# GL42.net
KiCad netlist of a schematic drawn in EAGLE
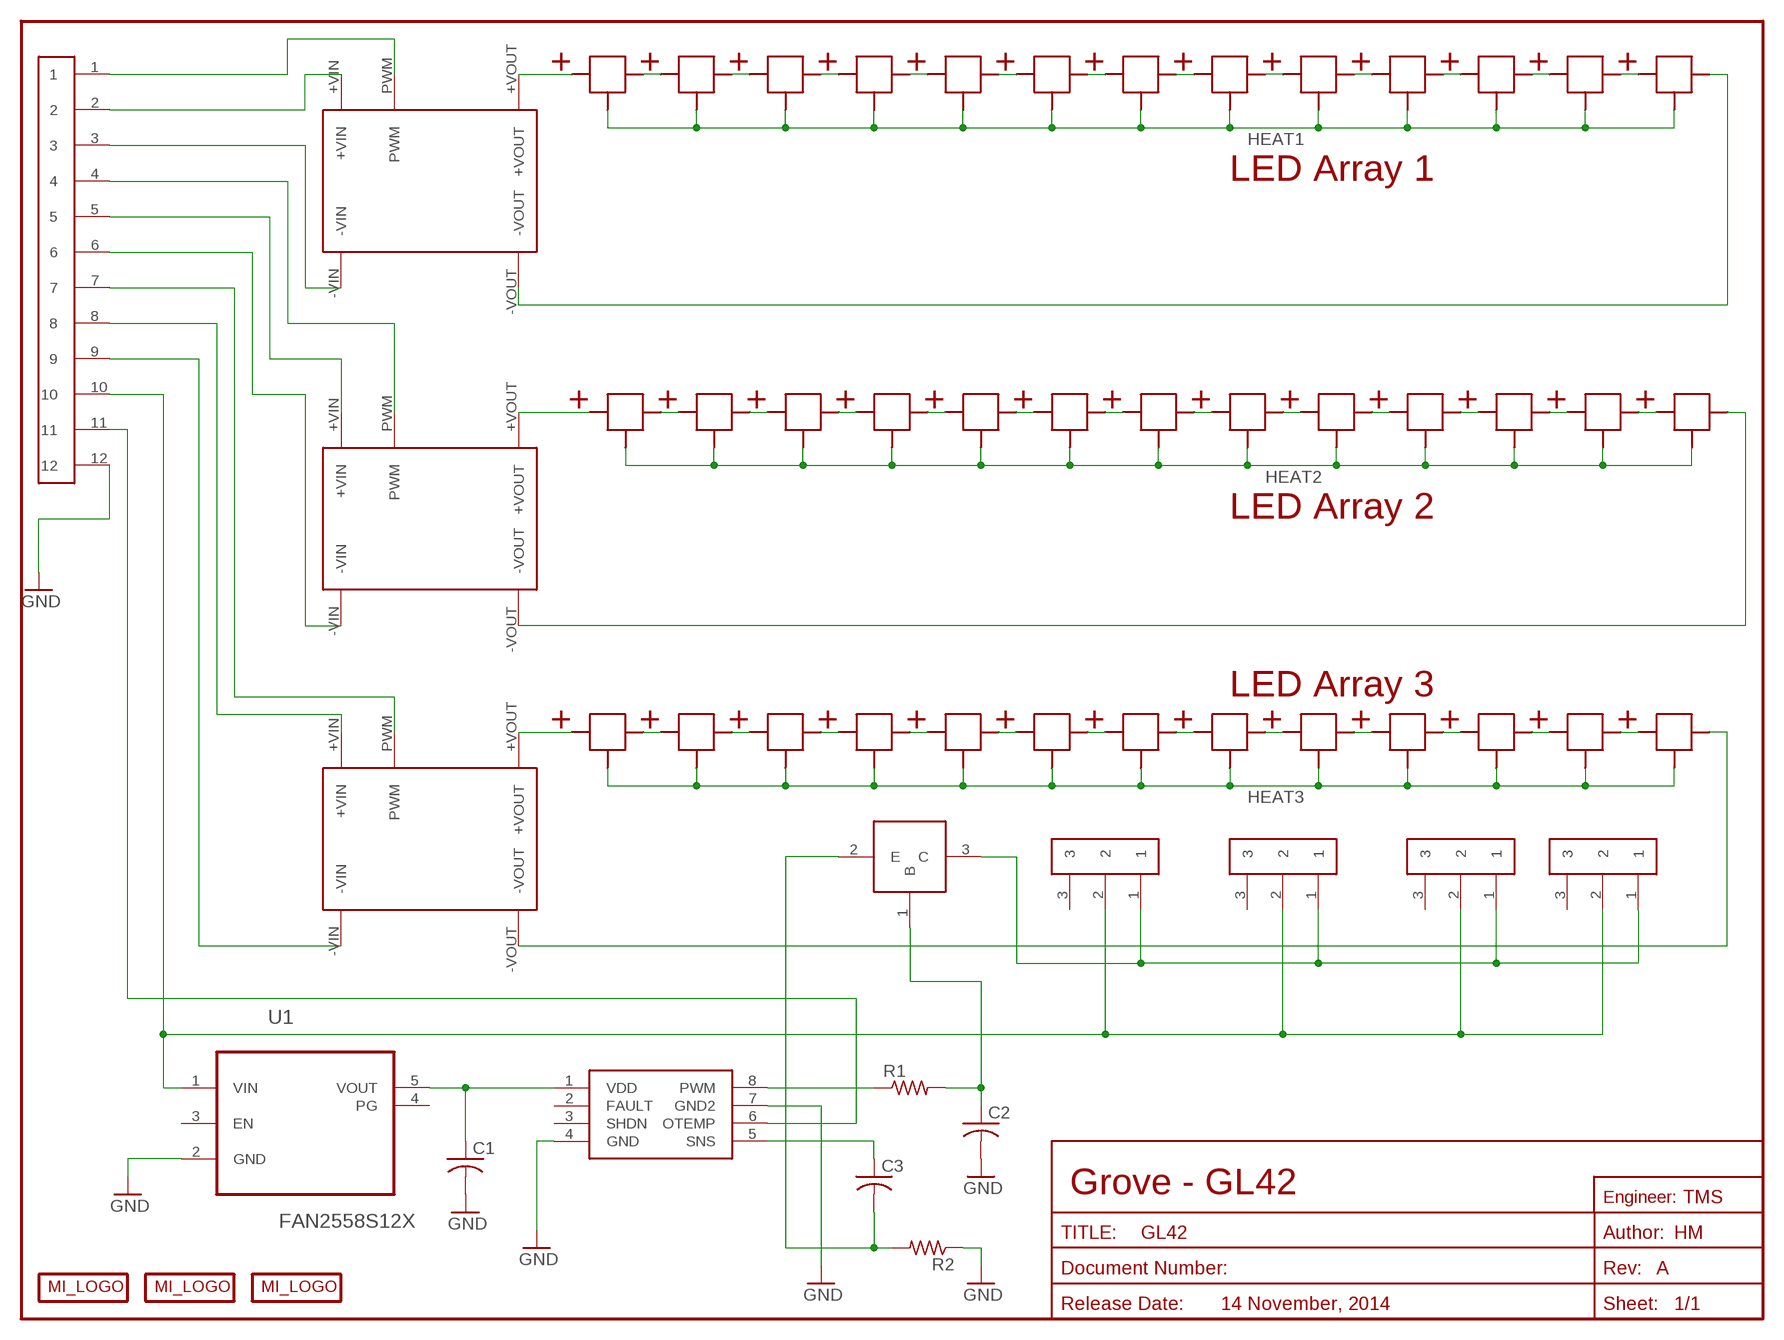
[diagram p0: schematic, sheet 1]

(export (version "E")
  (design (tool "Eeschema 10.0.6"))
  (components
    (comp (ref "C1")
      (value "C-USC1206")
      (footprint "eagle-import:C1206")
      (libsource (lib "eagle-import") (part "C-USC1206"))
    )
    (comp (ref "C2")
      (value "C-USC1206")
      (footprint "eagle-import:C1206")
      (libsource (lib "eagle-import") (part "C-USC1206"))
    )
    (comp (ref "C3")
      (value "C-USC1206")
      (footprint "eagle-import:C1206")
      (libsource (lib "eagle-import") (part "C-USC1206"))
    )
    (comp (ref "R1")
      (value "R-US_R1206")
      (footprint "eagle-import:R1206")
      (libsource (lib "eagle-import") (part "R-US_R1206"))
    )
    (comp (ref "R2")
      (value "R-US_R2512")
      (footprint "eagle-import:R2512")
      (libsource (lib "eagle-import") (part "R-US_R2512"))
    )
    (comp (ref "U$1")
      (value "CREE_XP")
      (footprint "eagle-import:XP")
      (libsource (lib "eagle-import") (part "CREE_XP"))
    )
    (comp (ref "U$2")
      (value "CREE_XP")
      (footprint "eagle-import:XP")
      (libsource (lib "eagle-import") (part "CREE_XP"))
    )
    (comp (ref "U$3")
      (value "CREE_XP")
      (footprint "eagle-import:XP")
      (libsource (lib "eagle-import") (part "CREE_XP"))
    )
    (comp (ref "U$4")
      (value "CREE_XP")
      (footprint "eagle-import:XP")
      (libsource (lib "eagle-import") (part "CREE_XP"))
    )
    (comp (ref "U$5")
      (value "CREE_XP")
      (footprint "eagle-import:XP")
      (libsource (lib "eagle-import") (part "CREE_XP"))
    )
    (comp (ref "U$6")
      (value "CREE_XP")
      (footprint "eagle-import:XP")
      (libsource (lib "eagle-import") (part "CREE_XP"))
    )
    (comp (ref "U$7")
      (value "CREE_XP")
      (footprint "eagle-import:XP")
      (libsource (lib "eagle-import") (part "CREE_XP"))
    )
    (comp (ref "U$8")
      (value "CREE_XP")
      (footprint "eagle-import:XP")
      (libsource (lib "eagle-import") (part "CREE_XP"))
    )
    (comp (ref "U$9")
      (value "CREE_XP")
      (footprint "eagle-import:XP")
      (libsource (lib "eagle-import") (part "CREE_XP"))
    )
    (comp (ref "U$10")
      (value "CREE_XP")
      (footprint "eagle-import:XP")
      (libsource (lib "eagle-import") (part "CREE_XP"))
    )
    (comp (ref "U$11")
      (value "CREE_XP")
      (footprint "eagle-import:XP")
      (libsource (lib "eagle-import") (part "CREE_XP"))
    )
    (comp (ref "U$12")
      (value "CREE_XP")
      (footprint "eagle-import:XP")
      (libsource (lib "eagle-import") (part "CREE_XP"))
    )
    (comp (ref "U$13")
      (value "CREE_XP")
      (footprint "eagle-import:XP")
      (libsource (lib "eagle-import") (part "CREE_XP"))
    )
    (comp (ref "U$14")
      (value "TC652")
      (footprint "eagle-import:MSOP8")
      (libsource (lib "eagle-import") (part "TC652"))
    )
    (comp (ref "U$15")
      (value "PH14SMT")
      (footprint "eagle-import:PH14SMT")
      (libsource (lib "eagle-import") (part "PH14SMT"))
    )
    (comp (ref "U$16")
      (value "LDD_HSMT")
      (footprint "eagle-import:LDD_HSMT")
      (libsource (lib "eagle-import") (part "LDD_HSMT"))
    )
    (comp (ref "U$17")
      (value "LDD_HSMT")
      (footprint "eagle-import:LDD_HSMT")
      (libsource (lib "eagle-import") (part "LDD_HSMT"))
    )
    (comp (ref "U$18")
      (value "LDD_HSMT")
      (footprint "eagle-import:LDD_HSMT")
      (libsource (lib "eagle-import") (part "LDD_HSMT"))
    )
    (comp (ref "U$19")
      (value "CREE_XP")
      (footprint "eagle-import:XP")
      (libsource (lib "eagle-import") (part "CREE_XP"))
    )
    (comp (ref "U$20")
      (value "CREE_XP")
      (footprint "eagle-import:XP")
      (libsource (lib "eagle-import") (part "CREE_XP"))
    )
    (comp (ref "U$21")
      (value "CREE_XP")
      (footprint "eagle-import:XP")
      (libsource (lib "eagle-import") (part "CREE_XP"))
    )
    (comp (ref "U$22")
      (value "CREE_XP")
      (footprint "eagle-import:XP")
      (libsource (lib "eagle-import") (part "CREE_XP"))
    )
    (comp (ref "U$23")
      (value "CREE_XP")
      (footprint "eagle-import:XP")
      (libsource (lib "eagle-import") (part "CREE_XP"))
    )
    (comp (ref "U$24")
      (value "CREE_XP")
      (footprint "eagle-import:XP")
      (libsource (lib "eagle-import") (part "CREE_XP"))
    )
    (comp (ref "U$25")
      (value "CREE_XP")
      (footprint "eagle-import:XP")
      (libsource (lib "eagle-import") (part "CREE_XP"))
    )
    (comp (ref "U$26")
      (value "CREE_XP")
      (footprint "eagle-import:XP")
      (libsource (lib "eagle-import") (part "CREE_XP"))
    )
    (comp (ref "U$27")
      (value "CREE_XP")
      (footprint "eagle-import:XP")
      (libsource (lib "eagle-import") (part "CREE_XP"))
    )
    (comp (ref "U$28")
      (value "CREE_XP")
      (footprint "eagle-import:XP")
      (libsource (lib "eagle-import") (part "CREE_XP"))
    )
    (comp (ref "U$29")
      (value "CREE_XP")
      (footprint "eagle-import:XP")
      (libsource (lib "eagle-import") (part "CREE_XP"))
    )
    (comp (ref "U$30")
      (value "CREE_XP")
      (footprint "eagle-import:XP")
      (libsource (lib "eagle-import") (part "CREE_XP"))
    )
    (comp (ref "U$31")
      (value "CREE_XP")
      (footprint "eagle-import:XP")
      (libsource (lib "eagle-import") (part "CREE_XP"))
    )
    (comp (ref "U$32")
      (value "CREE_XP")
      (footprint "eagle-import:XP")
      (libsource (lib "eagle-import") (part "CREE_XP"))
    )
    (comp (ref "U$33")
      (value "CREE_XP")
      (footprint "eagle-import:XP")
      (libsource (lib "eagle-import") (part "CREE_XP"))
    )
    (comp (ref "U$34")
      (value "CREE_XP")
      (footprint "eagle-import:XP")
      (libsource (lib "eagle-import") (part "CREE_XP"))
    )
    (comp (ref "U$35")
      (value "CREE_XP")
      (footprint "eagle-import:XP")
      (libsource (lib "eagle-import") (part "CREE_XP"))
    )
    (comp (ref "U$36")
      (value "CREE_XP")
      (footprint "eagle-import:XP")
      (libsource (lib "eagle-import") (part "CREE_XP"))
    )
    (comp (ref "U$37")
      (value "CREE_XP")
      (footprint "eagle-import:XP")
      (libsource (lib "eagle-import") (part "CREE_XP"))
    )
    (comp (ref "U$38")
      (value "CREE_XP")
      (footprint "eagle-import:XP")
      (libsource (lib "eagle-import") (part "CREE_XP"))
    )
    (comp (ref "U$39")
      (value "CREE_XP")
      (footprint "eagle-import:XP")
      (libsource (lib "eagle-import") (part "CREE_XP"))
    )
    (comp (ref "U$40")
      (value "CREE_XP")
      (footprint "eagle-import:XP")
      (libsource (lib "eagle-import") (part "CREE_XP"))
    )
    (comp (ref "U$41")
      (value "CREE_XP")
      (footprint "eagle-import:XP")
      (libsource (lib "eagle-import") (part "CREE_XP"))
    )
    (comp (ref "U$42")
      (value "CREE_XP")
      (footprint "eagle-import:XP")
      (libsource (lib "eagle-import") (part "CREE_XP"))
    )
    (comp (ref "U$43")
      (value "CREE_XP")
      (footprint "eagle-import:XP")
      (libsource (lib "eagle-import") (part "CREE_XP"))
    )
    (comp (ref "U$44")
      (value "CREE_XP")
      (footprint "eagle-import:XP")
      (libsource (lib "eagle-import") (part "CREE_XP"))
    )
    (comp (ref "U$45")
      (value "NPN_POWERTRAN")
      (footprint "eagle-import:TO252")
      (libsource (lib "eagle-import") (part "NPN_POWERTRAN"))
    )
    (comp (ref "U$46")
      (value "PH3SMT")
      (footprint "eagle-import:PH3SMT")
      (libsource (lib "eagle-import") (part "PH3SMT"))
    )
    (comp (ref "U$47")
      (value "PH3SMT")
      (footprint "eagle-import:PH3SMT")
      (libsource (lib "eagle-import") (part "PH3SMT"))
    )
    (comp (ref "U$48")
      (value "PH3SMT")
      (footprint "eagle-import:PH3SMT")
      (libsource (lib "eagle-import") (part "PH3SMT"))
    )
    (comp (ref "U$49")
      (value "PH3SMT")
      (footprint "eagle-import:PH3SMT")
      (libsource (lib "eagle-import") (part "PH3SMT"))
    )
    (comp (ref "U$50")
      (value "MI_LOGO-GROVE")
      (footprint "eagle-import:GROVES_LOGO")
      (libsource (lib "eagle-import") (part "MI_LOGO-GROVE"))
    )
    (comp (ref "U$51")
      (value "MI_LOGO-NAME_TWO")
      (footprint "eagle-import:MI_LOGO_NAME_2")
      (libsource (lib "eagle-import") (part "MI_LOGO-NAME_TWO"))
    )
    (comp (ref "U$54")
      (value "MI_LOGO-2014_USA")
      (footprint "eagle-import:MACRIS_USA_LOGO")
      (libsource (lib "eagle-import") (part "MI_LOGO-2014_USA"))
    )
    (comp (ref "U1")
      (value "FAN2558S12X")
      (footprint "eagle-import:SOT95P280X145-5N")
      (libsource (lib "eagle-import") (part "FAN2558S12X"))
    )
  )
  (nets
    (net (code "1") (name "/HEAT1") (class "Default")
      (node (ref "U$1") (pin "THERMAL") (pinfunction "THERMAL_THERMAL") (pintype "bidirectional"))
      (node (ref "U$10") (pin "THERMAL") (pinfunction "THERMAL_THERMAL") (pintype "bidirectional"))
      (node (ref "U$11") (pin "THERMAL") (pinfunction "THERMAL_THERMAL") (pintype "bidirectional"))
      (node (ref "U$12") (pin "THERMAL") (pinfunction "THERMAL_THERMAL") (pintype "bidirectional"))
      (node (ref "U$13") (pin "THERMAL") (pinfunction "THERMAL_THERMAL") (pintype "bidirectional"))
      (node (ref "U$2") (pin "THERMAL") (pinfunction "THERMAL_THERMAL") (pintype "bidirectional"))
      (node (ref "U$3") (pin "THERMAL") (pinfunction "THERMAL_THERMAL") (pintype "bidirectional"))
      (node (ref "U$4") (pin "THERMAL") (pinfunction "THERMAL_THERMAL") (pintype "bidirectional"))
      (node (ref "U$5") (pin "THERMAL") (pinfunction "THERMAL_THERMAL") (pintype "bidirectional"))
      (node (ref "U$6") (pin "THERMAL") (pinfunction "THERMAL_THERMAL") (pintype "bidirectional"))
      (node (ref "U$7") (pin "THERMAL") (pinfunction "THERMAL_THERMAL") (pintype "bidirectional"))
      (node (ref "U$8") (pin "THERMAL") (pinfunction "THERMAL_THERMAL") (pintype "bidirectional"))
      (node (ref "U$9") (pin "THERMAL") (pinfunction "THERMAL_THERMAL") (pintype "bidirectional"))
    )
    (net (code "2") (name "/HEAT2") (class "Default")
      (node (ref "U$19") (pin "THERMAL") (pinfunction "THERMAL_THERMAL") (pintype "bidirectional"))
      (node (ref "U$20") (pin "THERMAL") (pinfunction "THERMAL_THERMAL") (pintype "bidirectional"))
      (node (ref "U$21") (pin "THERMAL") (pinfunction "THERMAL_THERMAL") (pintype "bidirectional"))
      (node (ref "U$22") (pin "THERMAL") (pinfunction "THERMAL_THERMAL") (pintype "bidirectional"))
      (node (ref "U$23") (pin "THERMAL") (pinfunction "THERMAL_THERMAL") (pintype "bidirectional"))
      (node (ref "U$24") (pin "THERMAL") (pinfunction "THERMAL_THERMAL") (pintype "bidirectional"))
      (node (ref "U$25") (pin "THERMAL") (pinfunction "THERMAL_THERMAL") (pintype "bidirectional"))
      (node (ref "U$26") (pin "THERMAL") (pinfunction "THERMAL_THERMAL") (pintype "bidirectional"))
      (node (ref "U$27") (pin "THERMAL") (pinfunction "THERMAL_THERMAL") (pintype "bidirectional"))
      (node (ref "U$28") (pin "THERMAL") (pinfunction "THERMAL_THERMAL") (pintype "bidirectional"))
      (node (ref "U$29") (pin "THERMAL") (pinfunction "THERMAL_THERMAL") (pintype "bidirectional"))
      (node (ref "U$30") (pin "THERMAL") (pinfunction "THERMAL_THERMAL") (pintype "bidirectional"))
      (node (ref "U$31") (pin "THERMAL") (pinfunction "THERMAL_THERMAL") (pintype "bidirectional"))
    )
    (net (code "3") (name "/HEAT3") (class "Default")
      (node (ref "U$32") (pin "THERMAL") (pinfunction "THERMAL_THERMAL") (pintype "bidirectional"))
      (node (ref "U$33") (pin "THERMAL") (pinfunction "THERMAL_THERMAL") (pintype "bidirectional"))
      (node (ref "U$34") (pin "THERMAL") (pinfunction "THERMAL_THERMAL") (pintype "bidirectional"))
      (node (ref "U$35") (pin "THERMAL") (pinfunction "THERMAL_THERMAL") (pintype "bidirectional"))
      (node (ref "U$36") (pin "THERMAL") (pinfunction "THERMAL_THERMAL") (pintype "bidirectional"))
      (node (ref "U$37") (pin "THERMAL") (pinfunction "THERMAL_THERMAL") (pintype "bidirectional"))
      (node (ref "U$38") (pin "THERMAL") (pinfunction "THERMAL_THERMAL") (pintype "bidirectional"))
      (node (ref "U$39") (pin "THERMAL") (pinfunction "THERMAL_THERMAL") (pintype "bidirectional"))
      (node (ref "U$40") (pin "THERMAL") (pinfunction "THERMAL_THERMAL") (pintype "bidirectional"))
      (node (ref "U$41") (pin "THERMAL") (pinfunction "THERMAL_THERMAL") (pintype "bidirectional"))
      (node (ref "U$42") (pin "THERMAL") (pinfunction "THERMAL_THERMAL") (pintype "bidirectional"))
      (node (ref "U$43") (pin "THERMAL") (pinfunction "THERMAL_THERMAL") (pintype "bidirectional"))
      (node (ref "U$44") (pin "THERMAL") (pinfunction "THERMAL_THERMAL") (pintype "bidirectional"))
    )
    (net (code "4") (name "GND") (class "Default")
      (node (ref "C1") (pin "2") (pinfunction "2_2") (pintype "passive"))
      (node (ref "C2") (pin "2") (pinfunction "2_2") (pintype "passive"))
      (node (ref "R2") (pin "1") (pinfunction "1_1") (pintype "passive"))
      (node (ref "U$14") (pin "4") (pinfunction "GND_4") (pintype "bidirectional"))
      (node (ref "U$14") (pin "7") (pinfunction "GND2_7") (pintype "bidirectional"))
      (node (ref "U$15") (pin "12") (pinfunction "12_12") (pintype "bidirectional"))
      (node (ref "U1") (pin "2") (pinfunction "GND_2") (pintype "passive"))
    )
    (net (code "5") (name "Net-(U$1-NEGATIVE-PadNEGATIVE1)") (class "Default")
      (node (ref "U$1") (pin "NEGATIVE") (pinfunction "NEGATIVE_NEGATIVE") (pintype "bidirectional"))
      (node (ref "U$1") (pin "NEGATIVE1") (pinfunction "NEGATIVE_NEGATIVE1") (pintype "bidirectional"))
      (node (ref "U$2") (pin "POSITIVE") (pinfunction "POSITIVE_POSITIVE") (pintype "bidirectional"))
      (node (ref "U$2") (pin "POSITIVE1") (pinfunction "POSITIVE_POSITIVE1") (pintype "bidirectional"))
    )
    (net (code "6") (name "Net-(U$1-POSITIVE-PadPOSITIVE1)") (class "Default")
      (node (ref "U$1") (pin "POSITIVE") (pinfunction "POSITIVE_POSITIVE") (pintype "bidirectional"))
      (node (ref "U$1") (pin "POSITIVE1") (pinfunction "POSITIVE_POSITIVE1") (pintype "bidirectional"))
      (node (ref "U$16") (pin "+VOUT") (pinfunction "+VOUT_+VOUT") (pintype "bidirectional"))
    )
    (net (code "7") (name "Net-(U$2-NEGATIVE-PadNEGATIVE1)") (class "Default")
      (node (ref "U$2") (pin "NEGATIVE") (pinfunction "NEGATIVE_NEGATIVE") (pintype "bidirectional"))
      (node (ref "U$2") (pin "NEGATIVE1") (pinfunction "NEGATIVE_NEGATIVE1") (pintype "bidirectional"))
      (node (ref "U$3") (pin "POSITIVE") (pinfunction "POSITIVE_POSITIVE") (pintype "bidirectional"))
      (node (ref "U$3") (pin "POSITIVE1") (pinfunction "POSITIVE_POSITIVE1") (pintype "bidirectional"))
    )
    (net (code "8") (name "Net-(U$3-NEGATIVE-PadNEGATIVE1)") (class "Default")
      (node (ref "U$3") (pin "NEGATIVE") (pinfunction "NEGATIVE_NEGATIVE") (pintype "bidirectional"))
      (node (ref "U$3") (pin "NEGATIVE1") (pinfunction "NEGATIVE_NEGATIVE1") (pintype "bidirectional"))
      (node (ref "U$4") (pin "POSITIVE") (pinfunction "POSITIVE_POSITIVE") (pintype "bidirectional"))
      (node (ref "U$4") (pin "POSITIVE1") (pinfunction "POSITIVE_POSITIVE1") (pintype "bidirectional"))
    )
    (net (code "9") (name "Net-(U$4-NEGATIVE-PadNEGATIVE1)") (class "Default")
      (node (ref "U$4") (pin "NEGATIVE") (pinfunction "NEGATIVE_NEGATIVE") (pintype "bidirectional"))
      (node (ref "U$4") (pin "NEGATIVE1") (pinfunction "NEGATIVE_NEGATIVE1") (pintype "bidirectional"))
      (node (ref "U$5") (pin "POSITIVE") (pinfunction "POSITIVE_POSITIVE") (pintype "bidirectional"))
      (node (ref "U$5") (pin "POSITIVE1") (pinfunction "POSITIVE_POSITIVE1") (pintype "bidirectional"))
    )
    (net (code "10") (name "Net-(U$5-NEGATIVE-PadNEGATIVE1)") (class "Default")
      (node (ref "U$5") (pin "NEGATIVE") (pinfunction "NEGATIVE_NEGATIVE") (pintype "bidirectional"))
      (node (ref "U$5") (pin "NEGATIVE1") (pinfunction "NEGATIVE_NEGATIVE1") (pintype "bidirectional"))
      (node (ref "U$6") (pin "POSITIVE") (pinfunction "POSITIVE_POSITIVE") (pintype "bidirectional"))
      (node (ref "U$6") (pin "POSITIVE1") (pinfunction "POSITIVE_POSITIVE1") (pintype "bidirectional"))
    )
    (net (code "11") (name "Net-(U$6-NEGATIVE-PadNEGATIVE1)") (class "Default")
      (node (ref "U$6") (pin "NEGATIVE") (pinfunction "NEGATIVE_NEGATIVE") (pintype "bidirectional"))
      (node (ref "U$6") (pin "NEGATIVE1") (pinfunction "NEGATIVE_NEGATIVE1") (pintype "bidirectional"))
      (node (ref "U$7") (pin "POSITIVE") (pinfunction "POSITIVE_POSITIVE") (pintype "bidirectional"))
      (node (ref "U$7") (pin "POSITIVE1") (pinfunction "POSITIVE_POSITIVE1") (pintype "bidirectional"))
    )
    (net (code "12") (name "Net-(U$7-NEGATIVE-PadNEGATIVE1)") (class "Default")
      (node (ref "U$7") (pin "NEGATIVE") (pinfunction "NEGATIVE_NEGATIVE") (pintype "bidirectional"))
      (node (ref "U$7") (pin "NEGATIVE1") (pinfunction "NEGATIVE_NEGATIVE1") (pintype "bidirectional"))
      (node (ref "U$8") (pin "POSITIVE") (pinfunction "POSITIVE_POSITIVE") (pintype "bidirectional"))
      (node (ref "U$8") (pin "POSITIVE1") (pinfunction "POSITIVE_POSITIVE1") (pintype "bidirectional"))
    )
    (net (code "13") (name "Net-(U$8-NEGATIVE-PadNEGATIVE1)") (class "Default")
      (node (ref "U$8") (pin "NEGATIVE") (pinfunction "NEGATIVE_NEGATIVE") (pintype "bidirectional"))
      (node (ref "U$8") (pin "NEGATIVE1") (pinfunction "NEGATIVE_NEGATIVE1") (pintype "bidirectional"))
      (node (ref "U$9") (pin "POSITIVE") (pinfunction "POSITIVE_POSITIVE") (pintype "bidirectional"))
      (node (ref "U$9") (pin "POSITIVE1") (pinfunction "POSITIVE_POSITIVE1") (pintype "bidirectional"))
    )
    (net (code "14") (name "Net-(U$10-NEGATIVE-PadNEGATIVE1)") (class "Default")
      (node (ref "U$10") (pin "NEGATIVE") (pinfunction "NEGATIVE_NEGATIVE") (pintype "bidirectional"))
      (node (ref "U$10") (pin "NEGATIVE1") (pinfunction "NEGATIVE_NEGATIVE1") (pintype "bidirectional"))
      (node (ref "U$11") (pin "POSITIVE") (pinfunction "POSITIVE_POSITIVE") (pintype "bidirectional"))
      (node (ref "U$11") (pin "POSITIVE1") (pinfunction "POSITIVE_POSITIVE1") (pintype "bidirectional"))
    )
    (net (code "15") (name "Net-(U$10-POSITIVE-PadPOSITIVE1)") (class "Default")
      (node (ref "U$10") (pin "POSITIVE") (pinfunction "POSITIVE_POSITIVE") (pintype "bidirectional"))
      (node (ref "U$10") (pin "POSITIVE1") (pinfunction "POSITIVE_POSITIVE1") (pintype "bidirectional"))
      (node (ref "U$9") (pin "NEGATIVE") (pinfunction "NEGATIVE_NEGATIVE") (pintype "bidirectional"))
      (node (ref "U$9") (pin "NEGATIVE1") (pinfunction "NEGATIVE_NEGATIVE1") (pintype "bidirectional"))
    )
    (net (code "16") (name "Net-(U$11-NEGATIVE-PadNEGATIVE1)") (class "Default")
      (node (ref "U$11") (pin "NEGATIVE") (pinfunction "NEGATIVE_NEGATIVE") (pintype "bidirectional"))
      (node (ref "U$11") (pin "NEGATIVE1") (pinfunction "NEGATIVE_NEGATIVE1") (pintype "bidirectional"))
      (node (ref "U$12") (pin "POSITIVE") (pinfunction "POSITIVE_POSITIVE") (pintype "bidirectional"))
      (node (ref "U$12") (pin "POSITIVE1") (pinfunction "POSITIVE_POSITIVE1") (pintype "bidirectional"))
    )
    (net (code "17") (name "Net-(U$12-NEGATIVE-PadNEGATIVE1)") (class "Default")
      (node (ref "U$12") (pin "NEGATIVE") (pinfunction "NEGATIVE_NEGATIVE") (pintype "bidirectional"))
      (node (ref "U$12") (pin "NEGATIVE1") (pinfunction "NEGATIVE_NEGATIVE1") (pintype "bidirectional"))
      (node (ref "U$13") (pin "POSITIVE") (pinfunction "POSITIVE_POSITIVE") (pintype "bidirectional"))
      (node (ref "U$13") (pin "POSITIVE1") (pinfunction "POSITIVE_POSITIVE1") (pintype "bidirectional"))
    )
    (net (code "18") (name "Net-(U$13-NEGATIVE-PadNEGATIVE1)") (class "Default")
      (node (ref "U$13") (pin "NEGATIVE") (pinfunction "NEGATIVE_NEGATIVE") (pintype "bidirectional"))
      (node (ref "U$13") (pin "NEGATIVE1") (pinfunction "NEGATIVE_NEGATIVE1") (pintype "bidirectional"))
      (node (ref "U$16") (pin "-VOUT") (pinfunction "-VOUT_-VOUT") (pintype "bidirectional"))
    )
    (net (code "19") (name "Net-(U$14-OTEMP)") (class "Default")
      (node (ref "U$14") (pin "6") (pinfunction "OTEMP_6") (pintype "bidirectional"))
      (node (ref "U$15") (pin "11") (pinfunction "11_11") (pintype "bidirectional"))
    )
    (net (code "20") (name "Net-(U$14-PWM)") (class "Default")
      (node (ref "R1") (pin "1") (pinfunction "1_1") (pintype "passive"))
      (node (ref "U$14") (pin "8") (pinfunction "PWM_8") (pintype "bidirectional"))
    )
    (net (code "21") (name "Net-(U$14-SNS)") (class "Default")
      (node (ref "C3") (pin "1") (pinfunction "1_1") (pintype "passive"))
      (node (ref "U$14") (pin "5") (pinfunction "SNS_5") (pintype "bidirectional"))
    )
    (net (code "22") (name "Net-(U$14-VDD)") (class "Default")
      (node (ref "C1") (pin "1") (pinfunction "1_1") (pintype "passive"))
      (node (ref "U$14") (pin "1") (pinfunction "VDD_1") (pintype "bidirectional"))
      (node (ref "U1") (pin "5") (pinfunction "VOUT_5") (pintype "output"))
    )
    (net (code "23") (name "Net-(U$15-Pad1)") (class "Default")
      (node (ref "U$15") (pin "1") (pinfunction "1_1") (pintype "bidirectional"))
      (node (ref "U$16") (pin "PWM") (pinfunction "PWM_PWM") (pintype "bidirectional"))
    )
    (net (code "24") (name "Net-(U$15-Pad2)") (class "Default")
      (node (ref "U$15") (pin "2") (pinfunction "2_2") (pintype "bidirectional"))
      (node (ref "U$16") (pin "+VIN") (pinfunction "+VIN_+VIN") (pintype "bidirectional"))
    )
    (net (code "25") (name "Net-(U$15-Pad3)") (class "Default")
      (node (ref "U$15") (pin "3") (pinfunction "3_3") (pintype "bidirectional"))
      (node (ref "U$16") (pin "-VIN") (pinfunction "-VIN_-VIN") (pintype "bidirectional"))
    )
    (net (code "26") (name "Net-(U$15-Pad4)") (class "Default")
      (node (ref "U$15") (pin "4") (pinfunction "4_4") (pintype "bidirectional"))
      (node (ref "U$17") (pin "PWM") (pinfunction "PWM_PWM") (pintype "bidirectional"))
    )
    (net (code "27") (name "Net-(U$15-Pad5)") (class "Default")
      (node (ref "U$15") (pin "5") (pinfunction "5_5") (pintype "bidirectional"))
      (node (ref "U$17") (pin "+VIN") (pinfunction "+VIN_+VIN") (pintype "bidirectional"))
    )
    (net (code "28") (name "Net-(U$15-Pad6)") (class "Default")
      (node (ref "U$15") (pin "6") (pinfunction "6_6") (pintype "bidirectional"))
      (node (ref "U$17") (pin "-VIN") (pinfunction "-VIN_-VIN") (pintype "bidirectional"))
    )
    (net (code "29") (name "Net-(U$15-Pad7)") (class "Default")
      (node (ref "U$15") (pin "7") (pinfunction "7_7") (pintype "bidirectional"))
      (node (ref "U$18") (pin "PWM") (pinfunction "PWM_PWM") (pintype "bidirectional"))
    )
    (net (code "30") (name "Net-(U$15-Pad8)") (class "Default")
      (node (ref "U$15") (pin "8") (pinfunction "8_8") (pintype "bidirectional"))
      (node (ref "U$18") (pin "+VIN") (pinfunction "+VIN_+VIN") (pintype "bidirectional"))
    )
    (net (code "31") (name "Net-(U$15-Pad9)") (class "Default")
      (node (ref "U$15") (pin "9") (pinfunction "9_9") (pintype "bidirectional"))
      (node (ref "U$18") (pin "-VIN") (pinfunction "-VIN_-VIN") (pintype "bidirectional"))
    )
    (net (code "32") (name "Net-(U$17-Pad+VOUT)") (class "Default")
      (node (ref "U$17") (pin "+VOUT") (pinfunction "+VOUT_+VOUT") (pintype "bidirectional"))
      (node (ref "U$19") (pin "POSITIVE") (pinfunction "POSITIVE_POSITIVE") (pintype "bidirectional"))
      (node (ref "U$19") (pin "POSITIVE1") (pinfunction "POSITIVE_POSITIVE1") (pintype "bidirectional"))
    )
    (net (code "33") (name "Net-(U$17-Pad-VOUT)") (class "Default")
      (node (ref "U$17") (pin "-VOUT") (pinfunction "-VOUT_-VOUT") (pintype "bidirectional"))
      (node (ref "U$31") (pin "NEGATIVE") (pinfunction "NEGATIVE_NEGATIVE") (pintype "bidirectional"))
      (node (ref "U$31") (pin "NEGATIVE1") (pinfunction "NEGATIVE_NEGATIVE1") (pintype "bidirectional"))
    )
    (net (code "34") (name "Net-(U$18-Pad+VOUT)") (class "Default")
      (node (ref "U$18") (pin "+VOUT") (pinfunction "+VOUT_+VOUT") (pintype "bidirectional"))
      (node (ref "U$32") (pin "POSITIVE") (pinfunction "POSITIVE_POSITIVE") (pintype "bidirectional"))
      (node (ref "U$32") (pin "POSITIVE1") (pinfunction "POSITIVE_POSITIVE1") (pintype "bidirectional"))
    )
    (net (code "35") (name "Net-(U$18-Pad-VOUT)") (class "Default")
      (node (ref "U$18") (pin "-VOUT") (pinfunction "-VOUT_-VOUT") (pintype "bidirectional"))
      (node (ref "U$44") (pin "NEGATIVE") (pinfunction "NEGATIVE_NEGATIVE") (pintype "bidirectional"))
      (node (ref "U$44") (pin "NEGATIVE1") (pinfunction "NEGATIVE_NEGATIVE1") (pintype "bidirectional"))
    )
    (net (code "36") (name "Net-(U$19-NEGATIVE-PadNEGATIVE1)") (class "Default")
      (node (ref "U$19") (pin "NEGATIVE") (pinfunction "NEGATIVE_NEGATIVE") (pintype "bidirectional"))
      (node (ref "U$19") (pin "NEGATIVE1") (pinfunction "NEGATIVE_NEGATIVE1") (pintype "bidirectional"))
      (node (ref "U$20") (pin "POSITIVE") (pinfunction "POSITIVE_POSITIVE") (pintype "bidirectional"))
      (node (ref "U$20") (pin "POSITIVE1") (pinfunction "POSITIVE_POSITIVE1") (pintype "bidirectional"))
    )
    (net (code "37") (name "Net-(U$20-NEGATIVE-PadNEGATIVE1)") (class "Default")
      (node (ref "U$20") (pin "NEGATIVE") (pinfunction "NEGATIVE_NEGATIVE") (pintype "bidirectional"))
      (node (ref "U$20") (pin "NEGATIVE1") (pinfunction "NEGATIVE_NEGATIVE1") (pintype "bidirectional"))
      (node (ref "U$21") (pin "POSITIVE") (pinfunction "POSITIVE_POSITIVE") (pintype "bidirectional"))
      (node (ref "U$21") (pin "POSITIVE1") (pinfunction "POSITIVE_POSITIVE1") (pintype "bidirectional"))
    )
    (net (code "38") (name "Net-(U$21-NEGATIVE-PadNEGATIVE1)") (class "Default")
      (node (ref "U$21") (pin "NEGATIVE") (pinfunction "NEGATIVE_NEGATIVE") (pintype "bidirectional"))
      (node (ref "U$21") (pin "NEGATIVE1") (pinfunction "NEGATIVE_NEGATIVE1") (pintype "bidirectional"))
      (node (ref "U$22") (pin "POSITIVE") (pinfunction "POSITIVE_POSITIVE") (pintype "bidirectional"))
      (node (ref "U$22") (pin "POSITIVE1") (pinfunction "POSITIVE_POSITIVE1") (pintype "bidirectional"))
    )
    (net (code "39") (name "Net-(U$22-NEGATIVE-PadNEGATIVE1)") (class "Default")
      (node (ref "U$22") (pin "NEGATIVE") (pinfunction "NEGATIVE_NEGATIVE") (pintype "bidirectional"))
      (node (ref "U$22") (pin "NEGATIVE1") (pinfunction "NEGATIVE_NEGATIVE1") (pintype "bidirectional"))
      (node (ref "U$23") (pin "POSITIVE") (pinfunction "POSITIVE_POSITIVE") (pintype "bidirectional"))
      (node (ref "U$23") (pin "POSITIVE1") (pinfunction "POSITIVE_POSITIVE1") (pintype "bidirectional"))
    )
    (net (code "40") (name "Net-(U$23-NEGATIVE-PadNEGATIVE1)") (class "Default")
      (node (ref "U$23") (pin "NEGATIVE") (pinfunction "NEGATIVE_NEGATIVE") (pintype "bidirectional"))
      (node (ref "U$23") (pin "NEGATIVE1") (pinfunction "NEGATIVE_NEGATIVE1") (pintype "bidirectional"))
      (node (ref "U$24") (pin "POSITIVE") (pinfunction "POSITIVE_POSITIVE") (pintype "bidirectional"))
      (node (ref "U$24") (pin "POSITIVE1") (pinfunction "POSITIVE_POSITIVE1") (pintype "bidirectional"))
    )
    (net (code "41") (name "Net-(U$24-NEGATIVE-PadNEGATIVE1)") (class "Default")
      (node (ref "U$24") (pin "NEGATIVE") (pinfunction "NEGATIVE_NEGATIVE") (pintype "bidirectional"))
      (node (ref "U$24") (pin "NEGATIVE1") (pinfunction "NEGATIVE_NEGATIVE1") (pintype "bidirectional"))
      (node (ref "U$25") (pin "POSITIVE") (pinfunction "POSITIVE_POSITIVE") (pintype "bidirectional"))
      (node (ref "U$25") (pin "POSITIVE1") (pinfunction "POSITIVE_POSITIVE1") (pintype "bidirectional"))
    )
    (net (code "42") (name "Net-(U$25-NEGATIVE-PadNEGATIVE1)") (class "Default")
      (node (ref "U$25") (pin "NEGATIVE") (pinfunction "NEGATIVE_NEGATIVE") (pintype "bidirectional"))
      (node (ref "U$25") (pin "NEGATIVE1") (pinfunction "NEGATIVE_NEGATIVE1") (pintype "bidirectional"))
      (node (ref "U$26") (pin "POSITIVE") (pinfunction "POSITIVE_POSITIVE") (pintype "bidirectional"))
      (node (ref "U$26") (pin "POSITIVE1") (pinfunction "POSITIVE_POSITIVE1") (pintype "bidirectional"))
    )
    (net (code "43") (name "Net-(U$26-NEGATIVE-PadNEGATIVE1)") (class "Default")
      (node (ref "U$26") (pin "NEGATIVE") (pinfunction "NEGATIVE_NEGATIVE") (pintype "bidirectional"))
      (node (ref "U$26") (pin "NEGATIVE1") (pinfunction "NEGATIVE_NEGATIVE1") (pintype "bidirectional"))
      (node (ref "U$27") (pin "POSITIVE") (pinfunction "POSITIVE_POSITIVE") (pintype "bidirectional"))
      (node (ref "U$27") (pin "POSITIVE1") (pinfunction "POSITIVE_POSITIVE1") (pintype "bidirectional"))
    )
    (net (code "44") (name "Net-(U$27-NEGATIVE-PadNEGATIVE1)") (class "Default")
      (node (ref "U$27") (pin "NEGATIVE") (pinfunction "NEGATIVE_NEGATIVE") (pintype "bidirectional"))
      (node (ref "U$27") (pin "NEGATIVE1") (pinfunction "NEGATIVE_NEGATIVE1") (pintype "bidirectional"))
      (node (ref "U$28") (pin "POSITIVE") (pinfunction "POSITIVE_POSITIVE") (pintype "bidirectional"))
      (node (ref "U$28") (pin "POSITIVE1") (pinfunction "POSITIVE_POSITIVE1") (pintype "bidirectional"))
    )
    (net (code "45") (name "Net-(U$28-NEGATIVE-PadNEGATIVE1)") (class "Default")
      (node (ref "U$28") (pin "NEGATIVE") (pinfunction "NEGATIVE_NEGATIVE") (pintype "bidirectional"))
      (node (ref "U$28") (pin "NEGATIVE1") (pinfunction "NEGATIVE_NEGATIVE1") (pintype "bidirectional"))
      (node (ref "U$29") (pin "POSITIVE") (pinfunction "POSITIVE_POSITIVE") (pintype "bidirectional"))
      (node (ref "U$29") (pin "POSITIVE1") (pinfunction "POSITIVE_POSITIVE1") (pintype "bidirectional"))
    )
    (net (code "46") (name "Net-(U$29-NEGATIVE-PadNEGATIVE1)") (class "Default")
      (node (ref "U$29") (pin "NEGATIVE") (pinfunction "NEGATIVE_NEGATIVE") (pintype "bidirectional"))
      (node (ref "U$29") (pin "NEGATIVE1") (pinfunction "NEGATIVE_NEGATIVE1") (pintype "bidirectional"))
      (node (ref "U$30") (pin "POSITIVE") (pinfunction "POSITIVE_POSITIVE") (pintype "bidirectional"))
      (node (ref "U$30") (pin "POSITIVE1") (pinfunction "POSITIVE_POSITIVE1") (pintype "bidirectional"))
    )
    (net (code "47") (name "Net-(U$30-NEGATIVE-PadNEGATIVE1)") (class "Default")
      (node (ref "U$30") (pin "NEGATIVE") (pinfunction "NEGATIVE_NEGATIVE") (pintype "bidirectional"))
      (node (ref "U$30") (pin "NEGATIVE1") (pinfunction "NEGATIVE_NEGATIVE1") (pintype "bidirectional"))
      (node (ref "U$31") (pin "POSITIVE") (pinfunction "POSITIVE_POSITIVE") (pintype "bidirectional"))
      (node (ref "U$31") (pin "POSITIVE1") (pinfunction "POSITIVE_POSITIVE1") (pintype "bidirectional"))
    )
    (net (code "48") (name "Net-(U$32-NEGATIVE-PadNEGATIVE1)") (class "Default")
      (node (ref "U$32") (pin "NEGATIVE") (pinfunction "NEGATIVE_NEGATIVE") (pintype "bidirectional"))
      (node (ref "U$32") (pin "NEGATIVE1") (pinfunction "NEGATIVE_NEGATIVE1") (pintype "bidirectional"))
      (node (ref "U$33") (pin "POSITIVE") (pinfunction "POSITIVE_POSITIVE") (pintype "bidirectional"))
      (node (ref "U$33") (pin "POSITIVE1") (pinfunction "POSITIVE_POSITIVE1") (pintype "bidirectional"))
    )
    (net (code "49") (name "Net-(U$33-NEGATIVE-PadNEGATIVE1)") (class "Default")
      (node (ref "U$33") (pin "NEGATIVE") (pinfunction "NEGATIVE_NEGATIVE") (pintype "bidirectional"))
      (node (ref "U$33") (pin "NEGATIVE1") (pinfunction "NEGATIVE_NEGATIVE1") (pintype "bidirectional"))
      (node (ref "U$34") (pin "POSITIVE") (pinfunction "POSITIVE_POSITIVE") (pintype "bidirectional"))
      (node (ref "U$34") (pin "POSITIVE1") (pinfunction "POSITIVE_POSITIVE1") (pintype "bidirectional"))
    )
    (net (code "50") (name "Net-(U$34-NEGATIVE-PadNEGATIVE1)") (class "Default")
      (node (ref "U$34") (pin "NEGATIVE") (pinfunction "NEGATIVE_NEGATIVE") (pintype "bidirectional"))
      (node (ref "U$34") (pin "NEGATIVE1") (pinfunction "NEGATIVE_NEGATIVE1") (pintype "bidirectional"))
      (node (ref "U$35") (pin "POSITIVE") (pinfunction "POSITIVE_POSITIVE") (pintype "bidirectional"))
      (node (ref "U$35") (pin "POSITIVE1") (pinfunction "POSITIVE_POSITIVE1") (pintype "bidirectional"))
    )
    (net (code "51") (name "Net-(U$35-NEGATIVE-PadNEGATIVE1)") (class "Default")
      (node (ref "U$35") (pin "NEGATIVE") (pinfunction "NEGATIVE_NEGATIVE") (pintype "bidirectional"))
      (node (ref "U$35") (pin "NEGATIVE1") (pinfunction "NEGATIVE_NEGATIVE1") (pintype "bidirectional"))
      (node (ref "U$36") (pin "POSITIVE") (pinfunction "POSITIVE_POSITIVE") (pintype "bidirectional"))
      (node (ref "U$36") (pin "POSITIVE1") (pinfunction "POSITIVE_POSITIVE1") (pintype "bidirectional"))
    )
    (net (code "52") (name "Net-(U$36-NEGATIVE-PadNEGATIVE1)") (class "Default")
      (node (ref "U$36") (pin "NEGATIVE") (pinfunction "NEGATIVE_NEGATIVE") (pintype "bidirectional"))
      (node (ref "U$36") (pin "NEGATIVE1") (pinfunction "NEGATIVE_NEGATIVE1") (pintype "bidirectional"))
      (node (ref "U$37") (pin "POSITIVE") (pinfunction "POSITIVE_POSITIVE") (pintype "bidirectional"))
      (node (ref "U$37") (pin "POSITIVE1") (pinfunction "POSITIVE_POSITIVE1") (pintype "bidirectional"))
    )
    (net (code "53") (name "Net-(U$37-NEGATIVE-PadNEGATIVE1)") (class "Default")
      (node (ref "U$37") (pin "NEGATIVE") (pinfunction "NEGATIVE_NEGATIVE") (pintype "bidirectional"))
      (node (ref "U$37") (pin "NEGATIVE1") (pinfunction "NEGATIVE_NEGATIVE1") (pintype "bidirectional"))
      (node (ref "U$38") (pin "POSITIVE") (pinfunction "POSITIVE_POSITIVE") (pintype "bidirectional"))
      (node (ref "U$38") (pin "POSITIVE1") (pinfunction "POSITIVE_POSITIVE1") (pintype "bidirectional"))
    )
    (net (code "54") (name "Net-(U$38-NEGATIVE-PadNEGATIVE1)") (class "Default")
      (node (ref "U$38") (pin "NEGATIVE") (pinfunction "NEGATIVE_NEGATIVE") (pintype "bidirectional"))
      (node (ref "U$38") (pin "NEGATIVE1") (pinfunction "NEGATIVE_NEGATIVE1") (pintype "bidirectional"))
      (node (ref "U$39") (pin "POSITIVE") (pinfunction "POSITIVE_POSITIVE") (pintype "bidirectional"))
      (node (ref "U$39") (pin "POSITIVE1") (pinfunction "POSITIVE_POSITIVE1") (pintype "bidirectional"))
    )
    (net (code "55") (name "Net-(U$39-NEGATIVE-PadNEGATIVE1)") (class "Default")
      (node (ref "U$39") (pin "NEGATIVE") (pinfunction "NEGATIVE_NEGATIVE") (pintype "bidirectional"))
      (node (ref "U$39") (pin "NEGATIVE1") (pinfunction "NEGATIVE_NEGATIVE1") (pintype "bidirectional"))
      (node (ref "U$40") (pin "POSITIVE") (pinfunction "POSITIVE_POSITIVE") (pintype "bidirectional"))
      (node (ref "U$40") (pin "POSITIVE1") (pinfunction "POSITIVE_POSITIVE1") (pintype "bidirectional"))
    )
    (net (code "56") (name "Net-(U$40-NEGATIVE-PadNEGATIVE1)") (class "Default")
      (node (ref "U$40") (pin "NEGATIVE") (pinfunction "NEGATIVE_NEGATIVE") (pintype "bidirectional"))
      (node (ref "U$40") (pin "NEGATIVE1") (pinfunction "NEGATIVE_NEGATIVE1") (pintype "bidirectional"))
      (node (ref "U$41") (pin "POSITIVE") (pinfunction "POSITIVE_POSITIVE") (pintype "bidirectional"))
      (node (ref "U$41") (pin "POSITIVE1") (pinfunction "POSITIVE_POSITIVE1") (pintype "bidirectional"))
    )
    (net (code "57") (name "Net-(U$41-NEGATIVE-PadNEGATIVE1)") (class "Default")
      (node (ref "U$41") (pin "NEGATIVE") (pinfunction "NEGATIVE_NEGATIVE") (pintype "bidirectional"))
      (node (ref "U$41") (pin "NEGATIVE1") (pinfunction "NEGATIVE_NEGATIVE1") (pintype "bidirectional"))
      (node (ref "U$42") (pin "POSITIVE") (pinfunction "POSITIVE_POSITIVE") (pintype "bidirectional"))
      (node (ref "U$42") (pin "POSITIVE1") (pinfunction "POSITIVE_POSITIVE1") (pintype "bidirectional"))
    )
    (net (code "58") (name "Net-(U$42-NEGATIVE-PadNEGATIVE1)") (class "Default")
      (node (ref "U$42") (pin "NEGATIVE") (pinfunction "NEGATIVE_NEGATIVE") (pintype "bidirectional"))
      (node (ref "U$42") (pin "NEGATIVE1") (pinfunction "NEGATIVE_NEGATIVE1") (pintype "bidirectional"))
      (node (ref "U$43") (pin "POSITIVE") (pinfunction "POSITIVE_POSITIVE") (pintype "bidirectional"))
      (node (ref "U$43") (pin "POSITIVE1") (pinfunction "POSITIVE_POSITIVE1") (pintype "bidirectional"))
    )
    (net (code "59") (name "Net-(U$43-NEGATIVE-PadNEGATIVE1)") (class "Default")
      (node (ref "U$43") (pin "NEGATIVE") (pinfunction "NEGATIVE_NEGATIVE") (pintype "bidirectional"))
      (node (ref "U$43") (pin "NEGATIVE1") (pinfunction "NEGATIVE_NEGATIVE1") (pintype "bidirectional"))
      (node (ref "U$44") (pin "POSITIVE") (pinfunction "POSITIVE_POSITIVE") (pintype "bidirectional"))
      (node (ref "U$44") (pin "POSITIVE1") (pinfunction "POSITIVE_POSITIVE1") (pintype "bidirectional"))
    )
    (net (code "60") (name "Net-(U$45-B)") (class "Default")
      (node (ref "C2") (pin "1") (pinfunction "1_1") (pintype "passive"))
      (node (ref "R1") (pin "2") (pinfunction "2_2") (pintype "passive"))
      (node (ref "U$45") (pin "1") (pinfunction "B_1") (pintype "bidirectional"))
    )
    (net (code "61") (name "Net-(U$45-C)") (class "Default")
      (node (ref "U$45") (pin "3") (pinfunction "C_3") (pintype "bidirectional"))
      (node (ref "U$46") (pin "1") (pinfunction "1_1") (pintype "bidirectional"))
      (node (ref "U$47") (pin "1") (pinfunction "1_1") (pintype "bidirectional"))
      (node (ref "U$48") (pin "1") (pinfunction "1_1") (pintype "bidirectional"))
      (node (ref "U$49") (pin "1") (pinfunction "1_1") (pintype "bidirectional"))
    )
    (net (code "62") (name "Net-(U$45-E)") (class "Default")
      (node (ref "C3") (pin "2") (pinfunction "2_2") (pintype "passive"))
      (node (ref "R2") (pin "2") (pinfunction "2_2") (pintype "passive"))
      (node (ref "U$45") (pin "2") (pinfunction "E_2") (pintype "bidirectional"))
    )
    (net (code "63") (name "Net-(U1-VIN)") (class "Default")
      (node (ref "U$15") (pin "10") (pinfunction "10_10") (pintype "bidirectional"))
      (node (ref "U$46") (pin "2") (pinfunction "2_2") (pintype "bidirectional"))
      (node (ref "U$47") (pin "2") (pinfunction "2_2") (pintype "bidirectional"))
      (node (ref "U$48") (pin "2") (pinfunction "2_2") (pintype "bidirectional"))
      (node (ref "U$49") (pin "2") (pinfunction "2_2") (pintype "bidirectional"))
      (node (ref "U1") (pin "1") (pinfunction "VIN_1") (pintype "power_in"))
    )
    (net (code "64") (name "unconnected-(U$14-FAULT-Pad2)") (class "Default")
      (node (ref "U$14") (pin "2") (pinfunction "FAULT_2") (pintype "bidirectional"))
    )
    (net (code "65") (name "unconnected-(U$14-SHDN-Pad3)") (class "Default")
      (node (ref "U$14") (pin "3") (pinfunction "SHDN_3") (pintype "bidirectional"))
    )
    (net (code "66") (name "unconnected-(U$46-Pad3)") (class "Default")
      (node (ref "U$46") (pin "3") (pinfunction "3_3") (pintype "bidirectional"))
    )
    (net (code "67") (name "unconnected-(U$47-Pad3)") (class "Default")
      (node (ref "U$47") (pin "3") (pinfunction "3_3") (pintype "bidirectional"))
    )
    (net (code "68") (name "unconnected-(U$48-Pad3)") (class "Default")
      (node (ref "U$48") (pin "3") (pinfunction "3_3") (pintype "bidirectional"))
    )
    (net (code "69") (name "unconnected-(U$49-Pad3)") (class "Default")
      (node (ref "U$49") (pin "3") (pinfunction "3_3") (pintype "bidirectional"))
    )
    (net (code "70") (name "unconnected-(U1-EN-Pad3)") (class "Default")
      (node (ref "U1") (pin "3") (pinfunction "EN_3") (pintype "input"))
    )
    (net (code "71") (name "unconnected-(U1-PG-Pad4)") (class "Default")
      (node (ref "U1") (pin "4") (pinfunction "PG_4") (pintype "output"))
    )
  )
)
